# KegWasher_12V_Abort_Filter_1_0_Schematic.net
KiCad netlist of a schematic drawn in EasyEDA
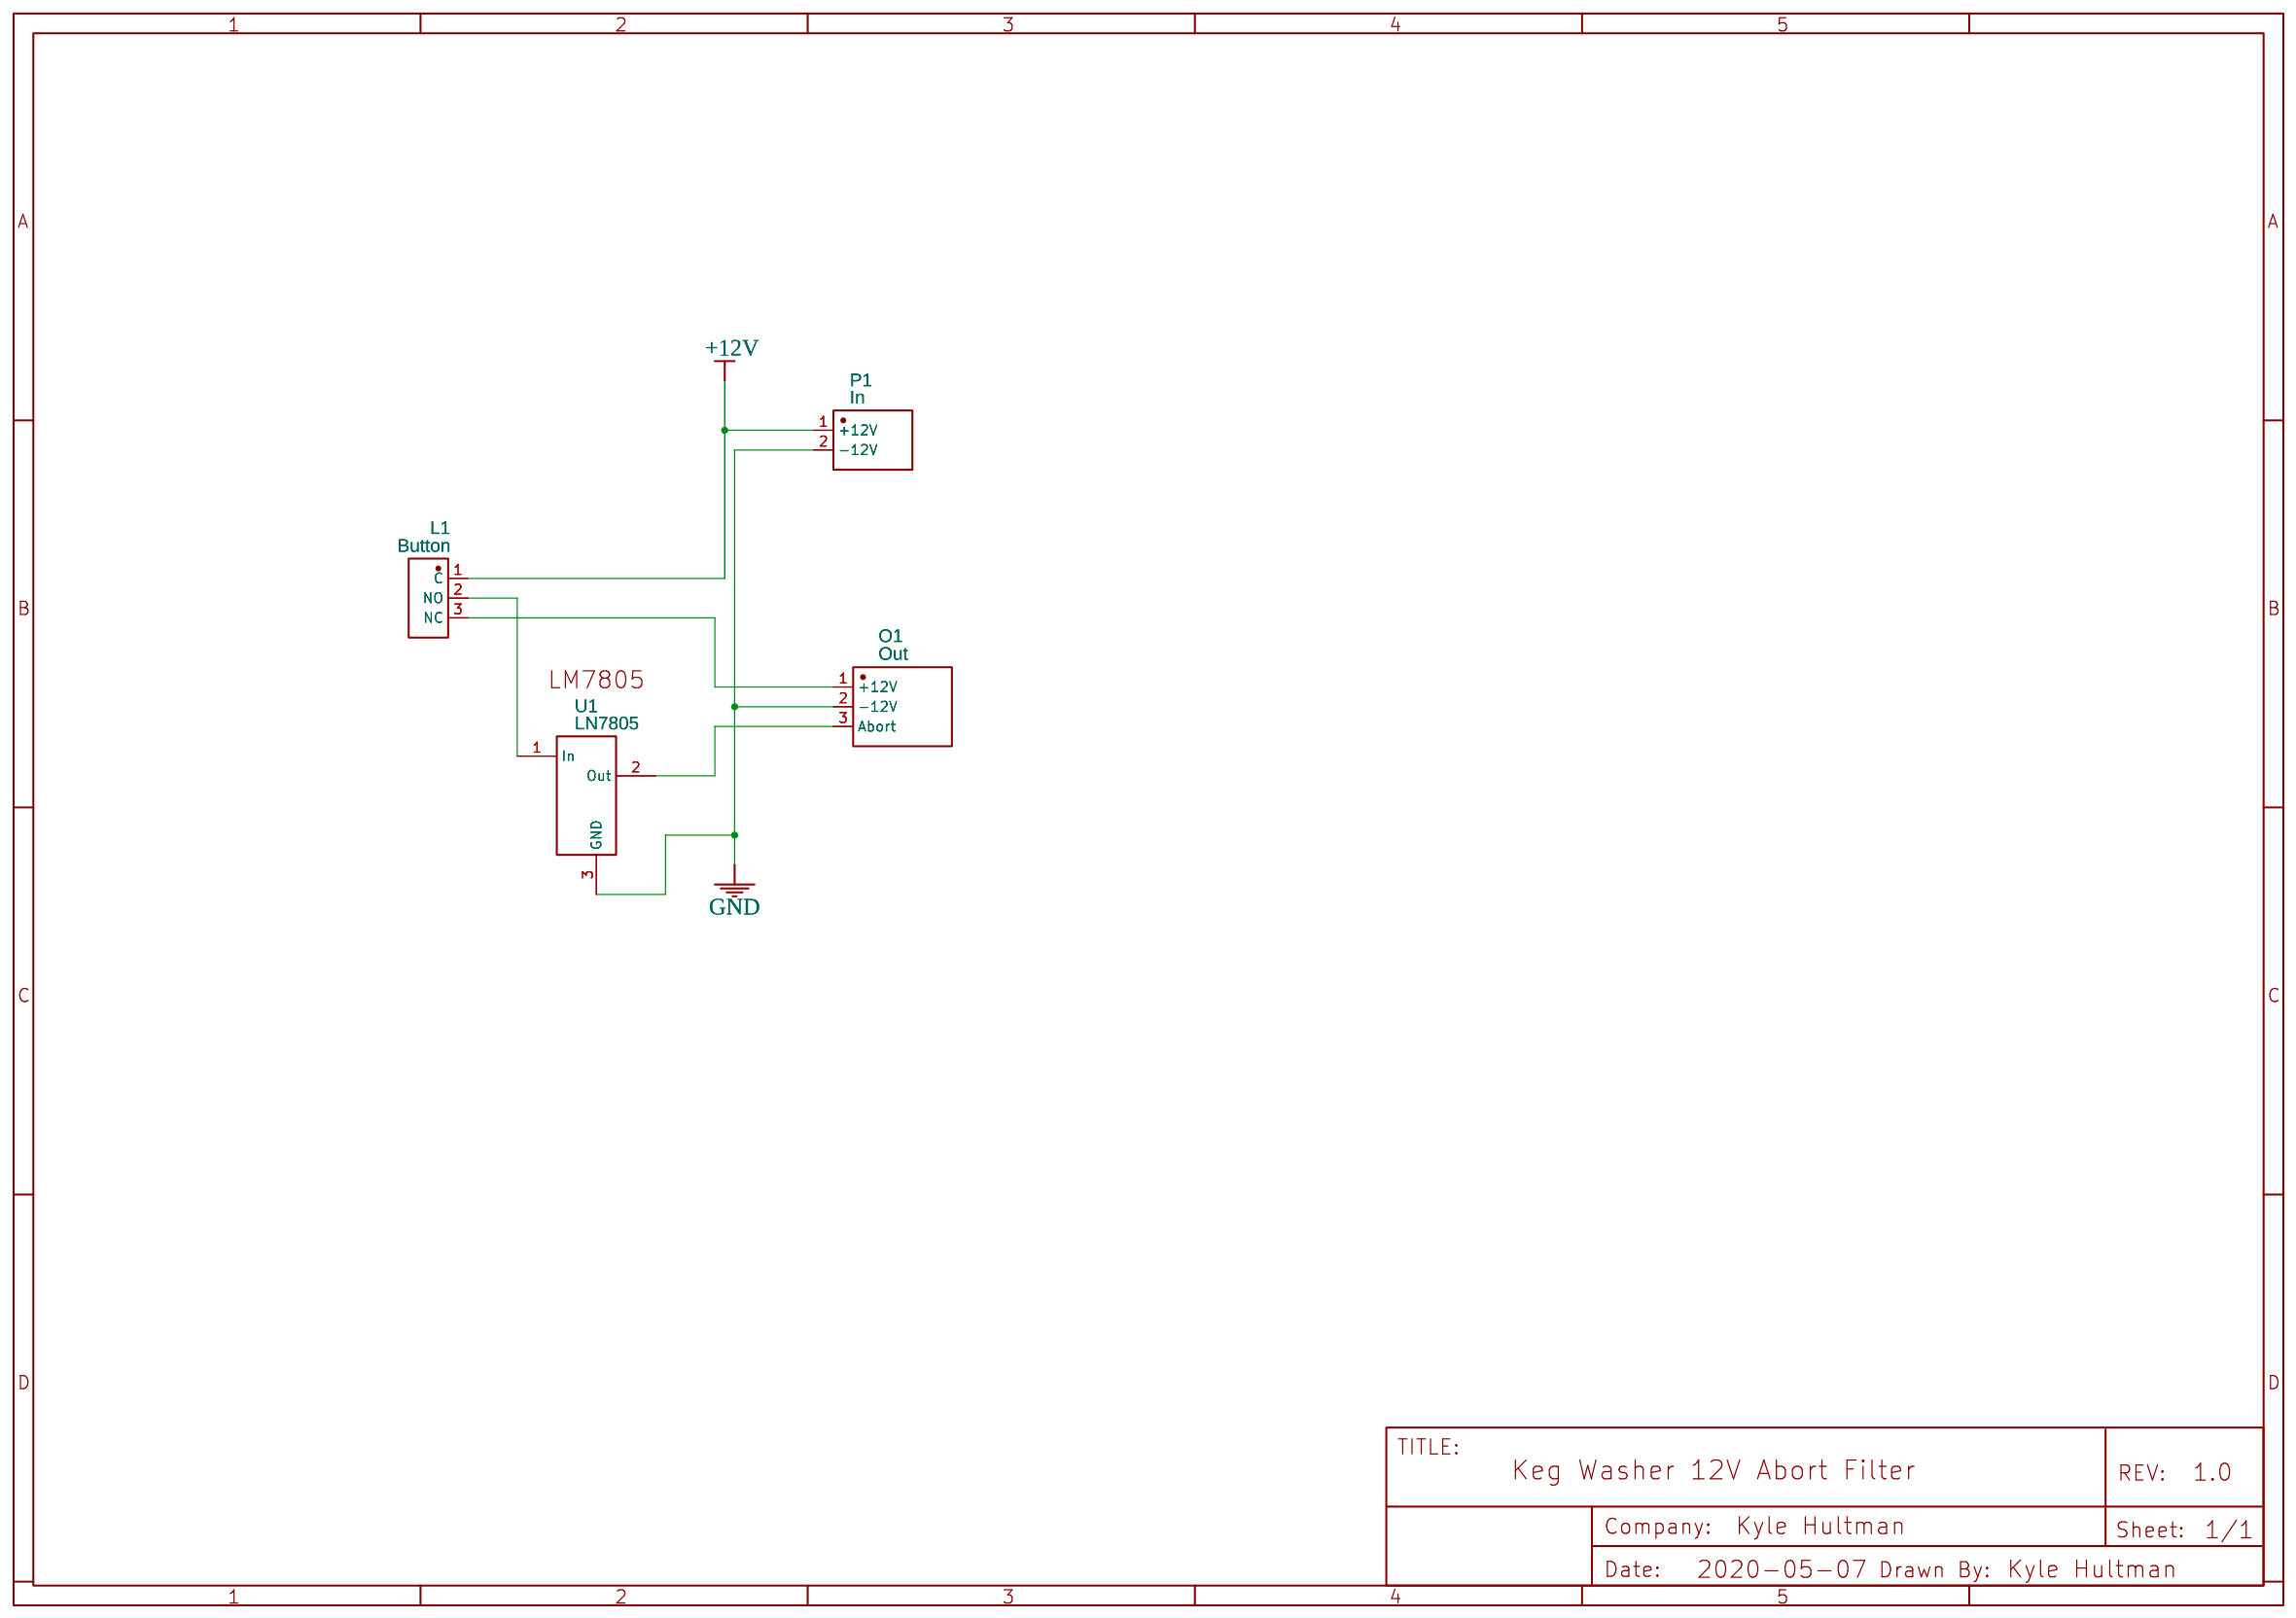
[diagram p0: schematic sheet]

(export (version "E")
  (design (tool "Eeschema 10.0.6"))
  (components
    (comp (ref "L1") (value "Button") (libsource (lib "") (part "Button")))
    (comp (ref "O1") (value "Out") (libsource (lib "") (part "Out")))
    (comp (ref "P1") (value "In") (libsource (lib "") (part "In")))
    (comp (ref "U1")
      (value "LN7805")
      (fields (field (name "BOM_Manufacturer Part") "Pollin"))
      (libsource (lib "") (part "LN7805"))
    )
  )
  (nets
    (net (code "1") (name "+12V") (class "Default")
      (node (ref "L1") (pin "1") (pinfunction "C_1") (pintype "unspecified"))
      (node (ref "P1") (pin "1") (pinfunction "+12V_1") (pintype "unspecified"))
    )
    (net (code "2") (name "GND") (class "Default")
      (node (ref "O1") (pin "2") (pinfunction "-12V_2") (pintype "unspecified"))
      (node (ref "P1") (pin "2") (pinfunction "-12V_2") (pintype "unspecified"))
      (node (ref "U1") (pin "3") (pinfunction "GND_3") (pintype "unspecified"))
    )
    (net (code "3") (name "Net-(L1-NC)") (class "Default")
      (node (ref "L1") (pin "3") (pinfunction "NC_3") (pintype "unspecified"))
      (node (ref "O1") (pin "1") (pinfunction "+12V_1") (pintype "unspecified"))
    )
    (net (code "4") (name "Net-(L1-NO)") (class "Default")
      (node (ref "L1") (pin "2") (pinfunction "NO_2") (pintype "unspecified"))
      (node (ref "U1") (pin "1") (pinfunction "In_1") (pintype "unspecified"))
    )
    (net (code "5") (name "Net-(O1-Abort)") (class "Default")
      (node (ref "O1") (pin "3") (pinfunction "Abort_3") (pintype "unspecified"))
      (node (ref "U1") (pin "2") (pinfunction "Out_2") (pintype "unspecified"))
    )
  )
)
